# Uno_v1_0.net
KiCad netlist of a schematic drawn in EAGLE
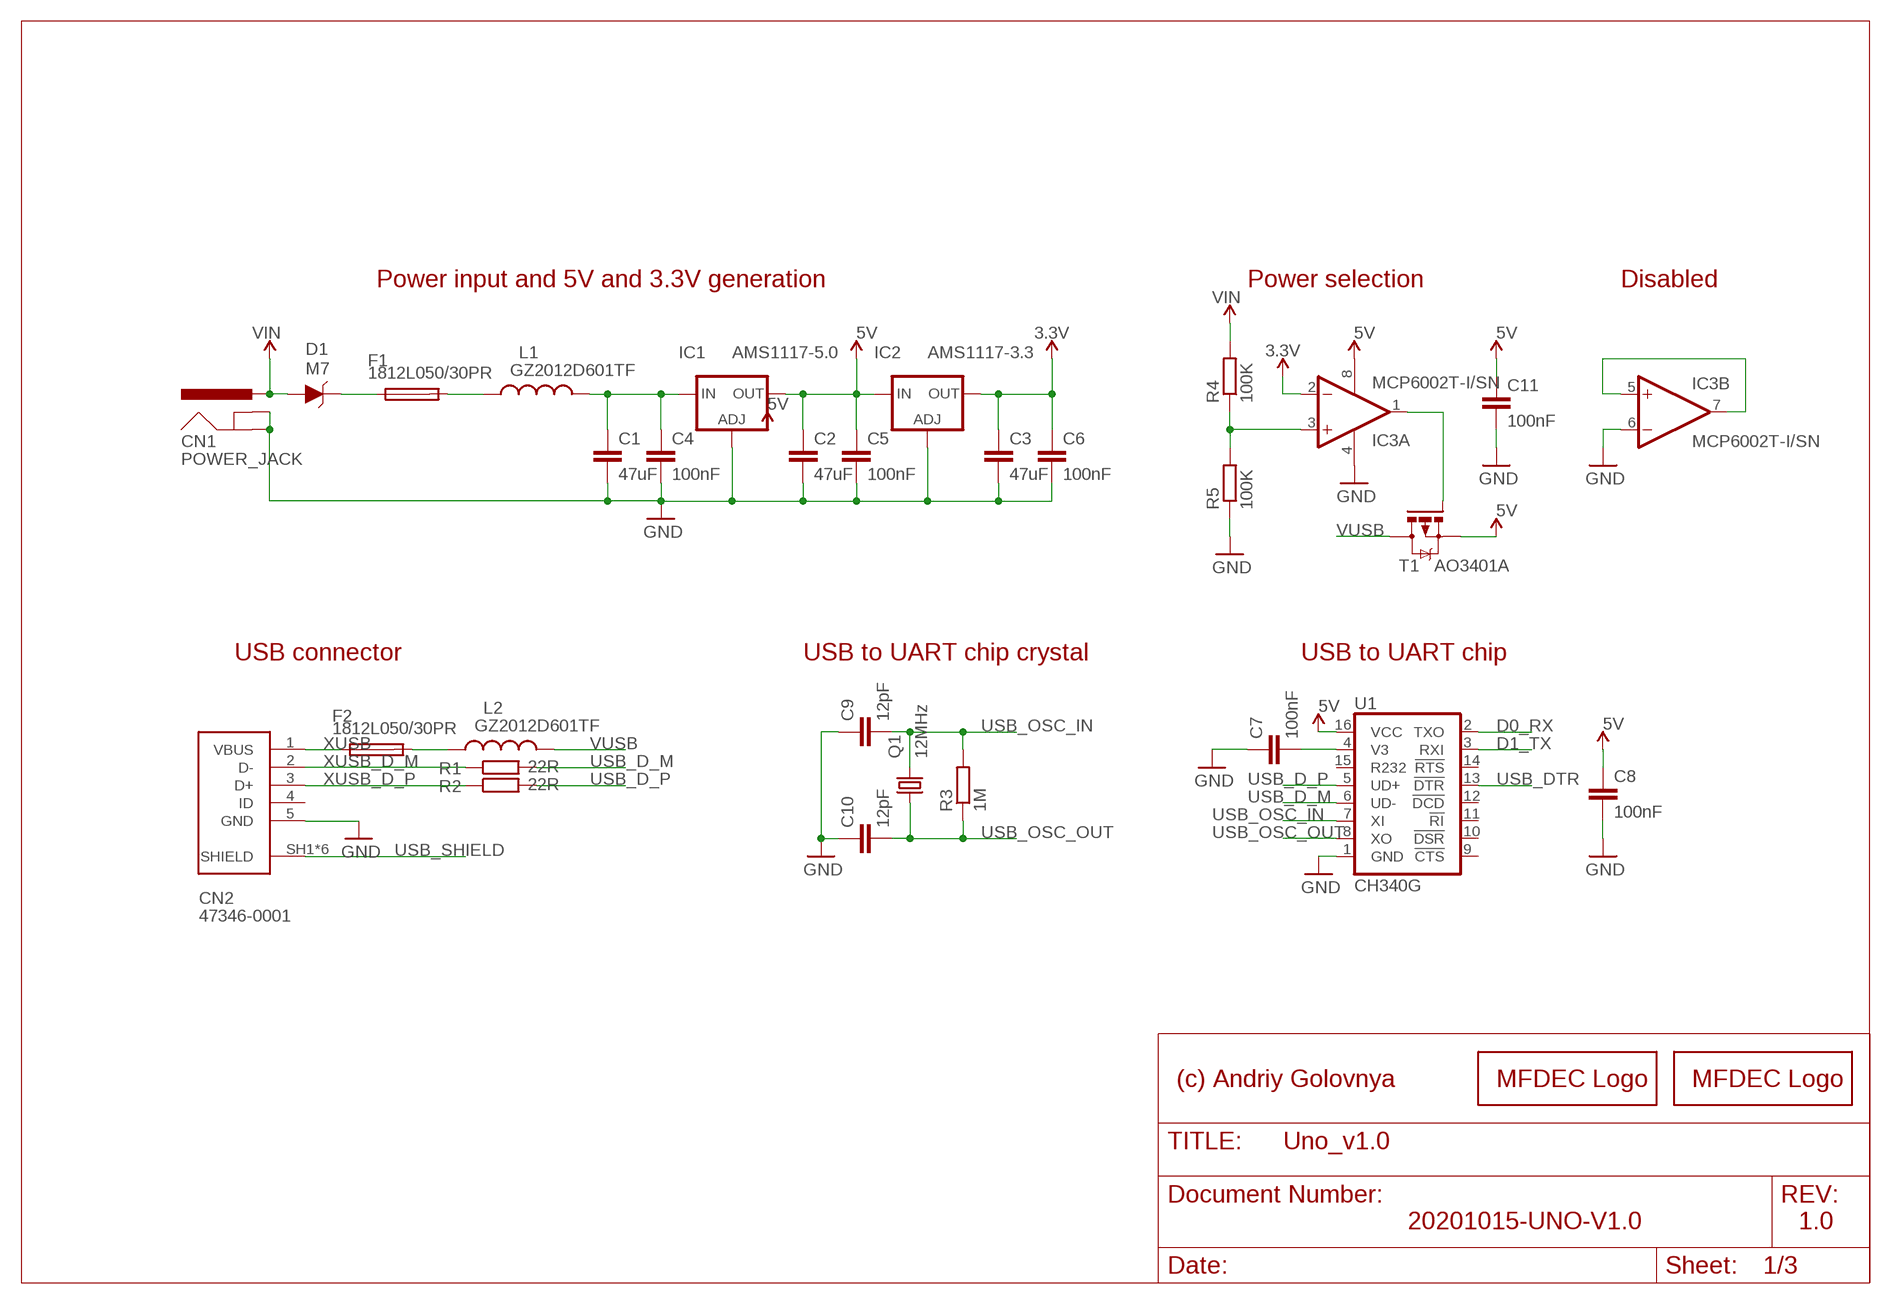
[diagram p0: schematic, sheet 1]
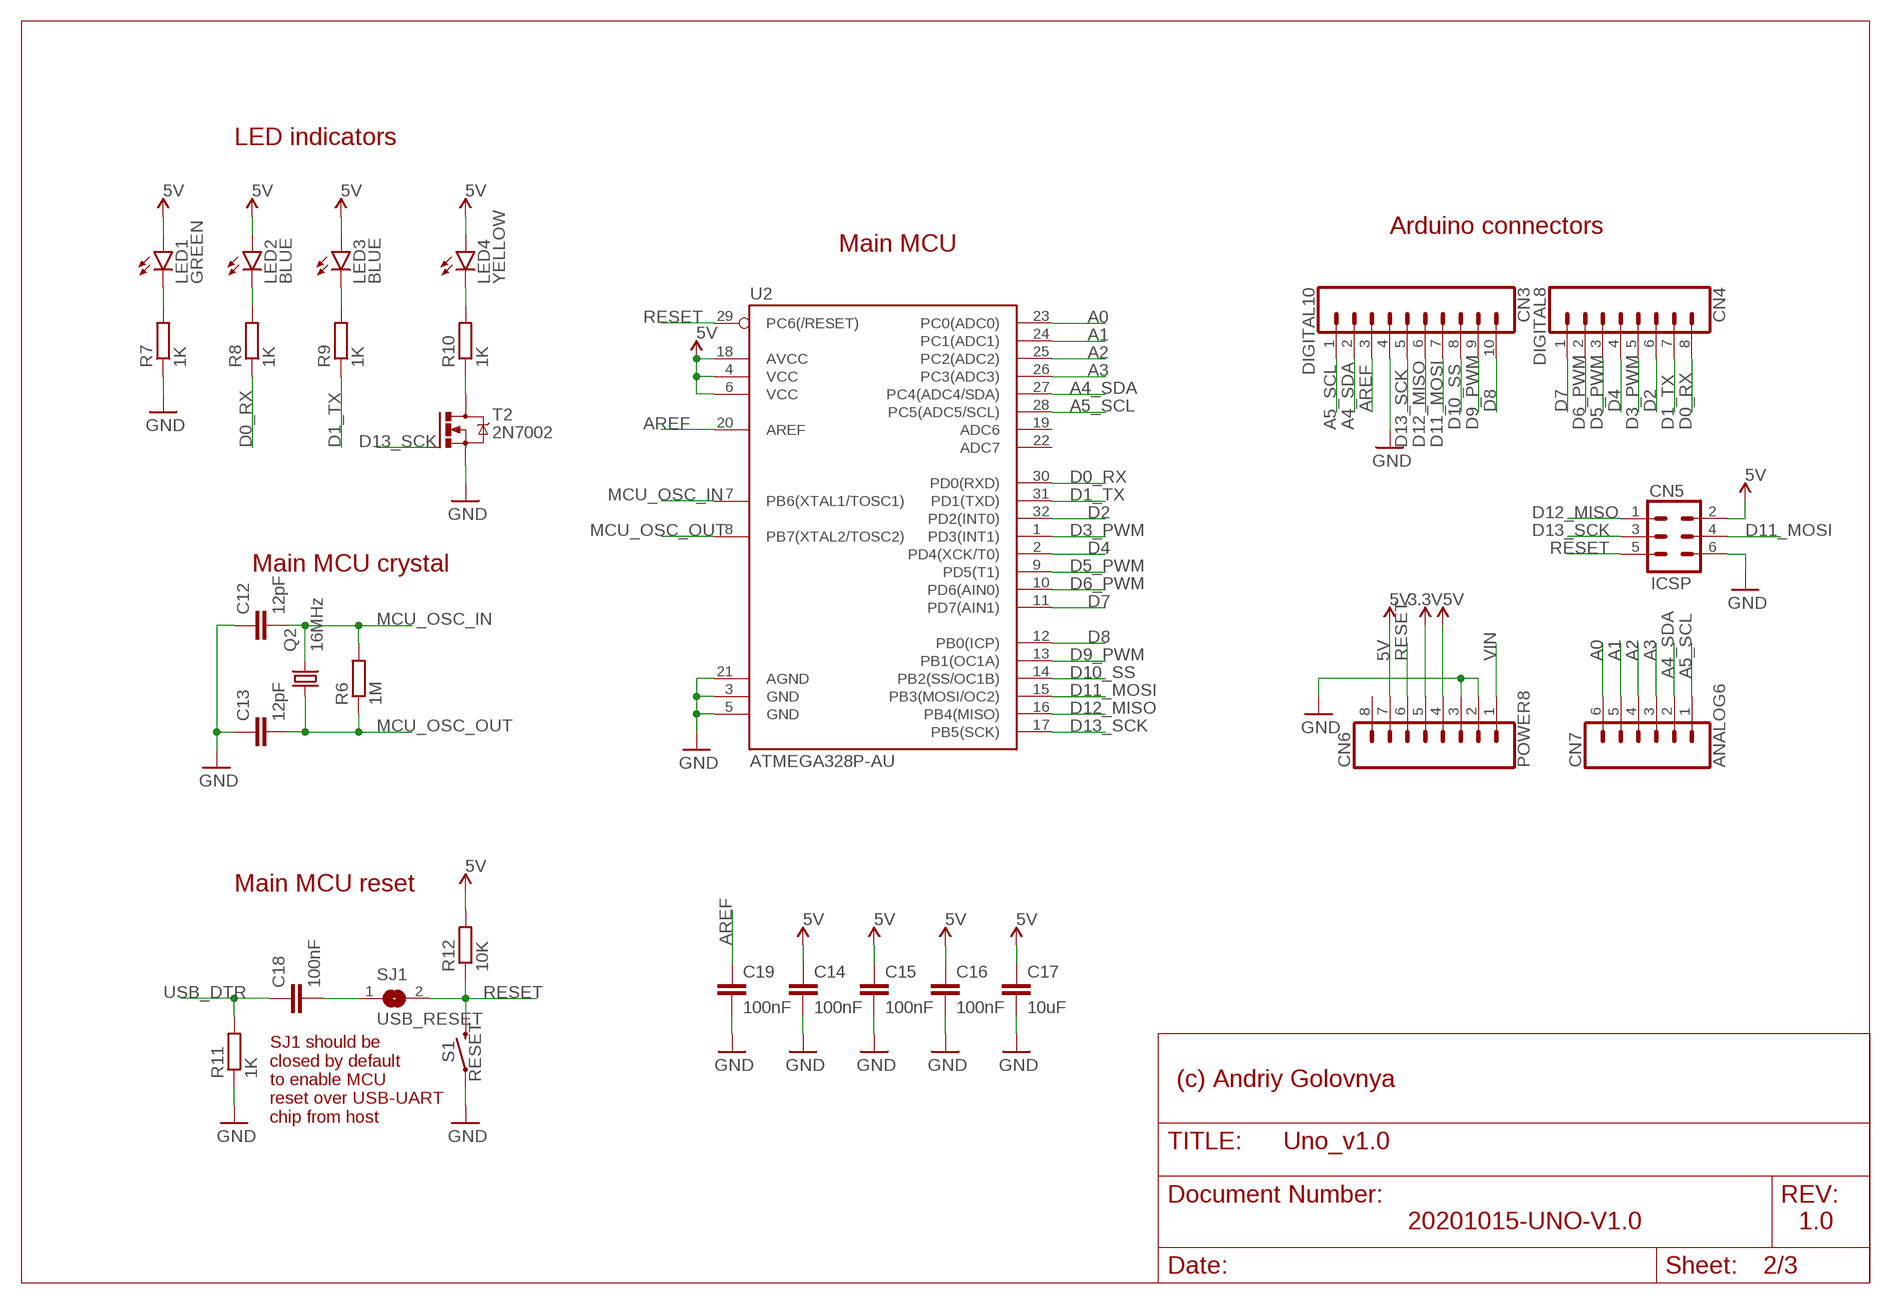
[diagram p1: schematic, sheet 2]
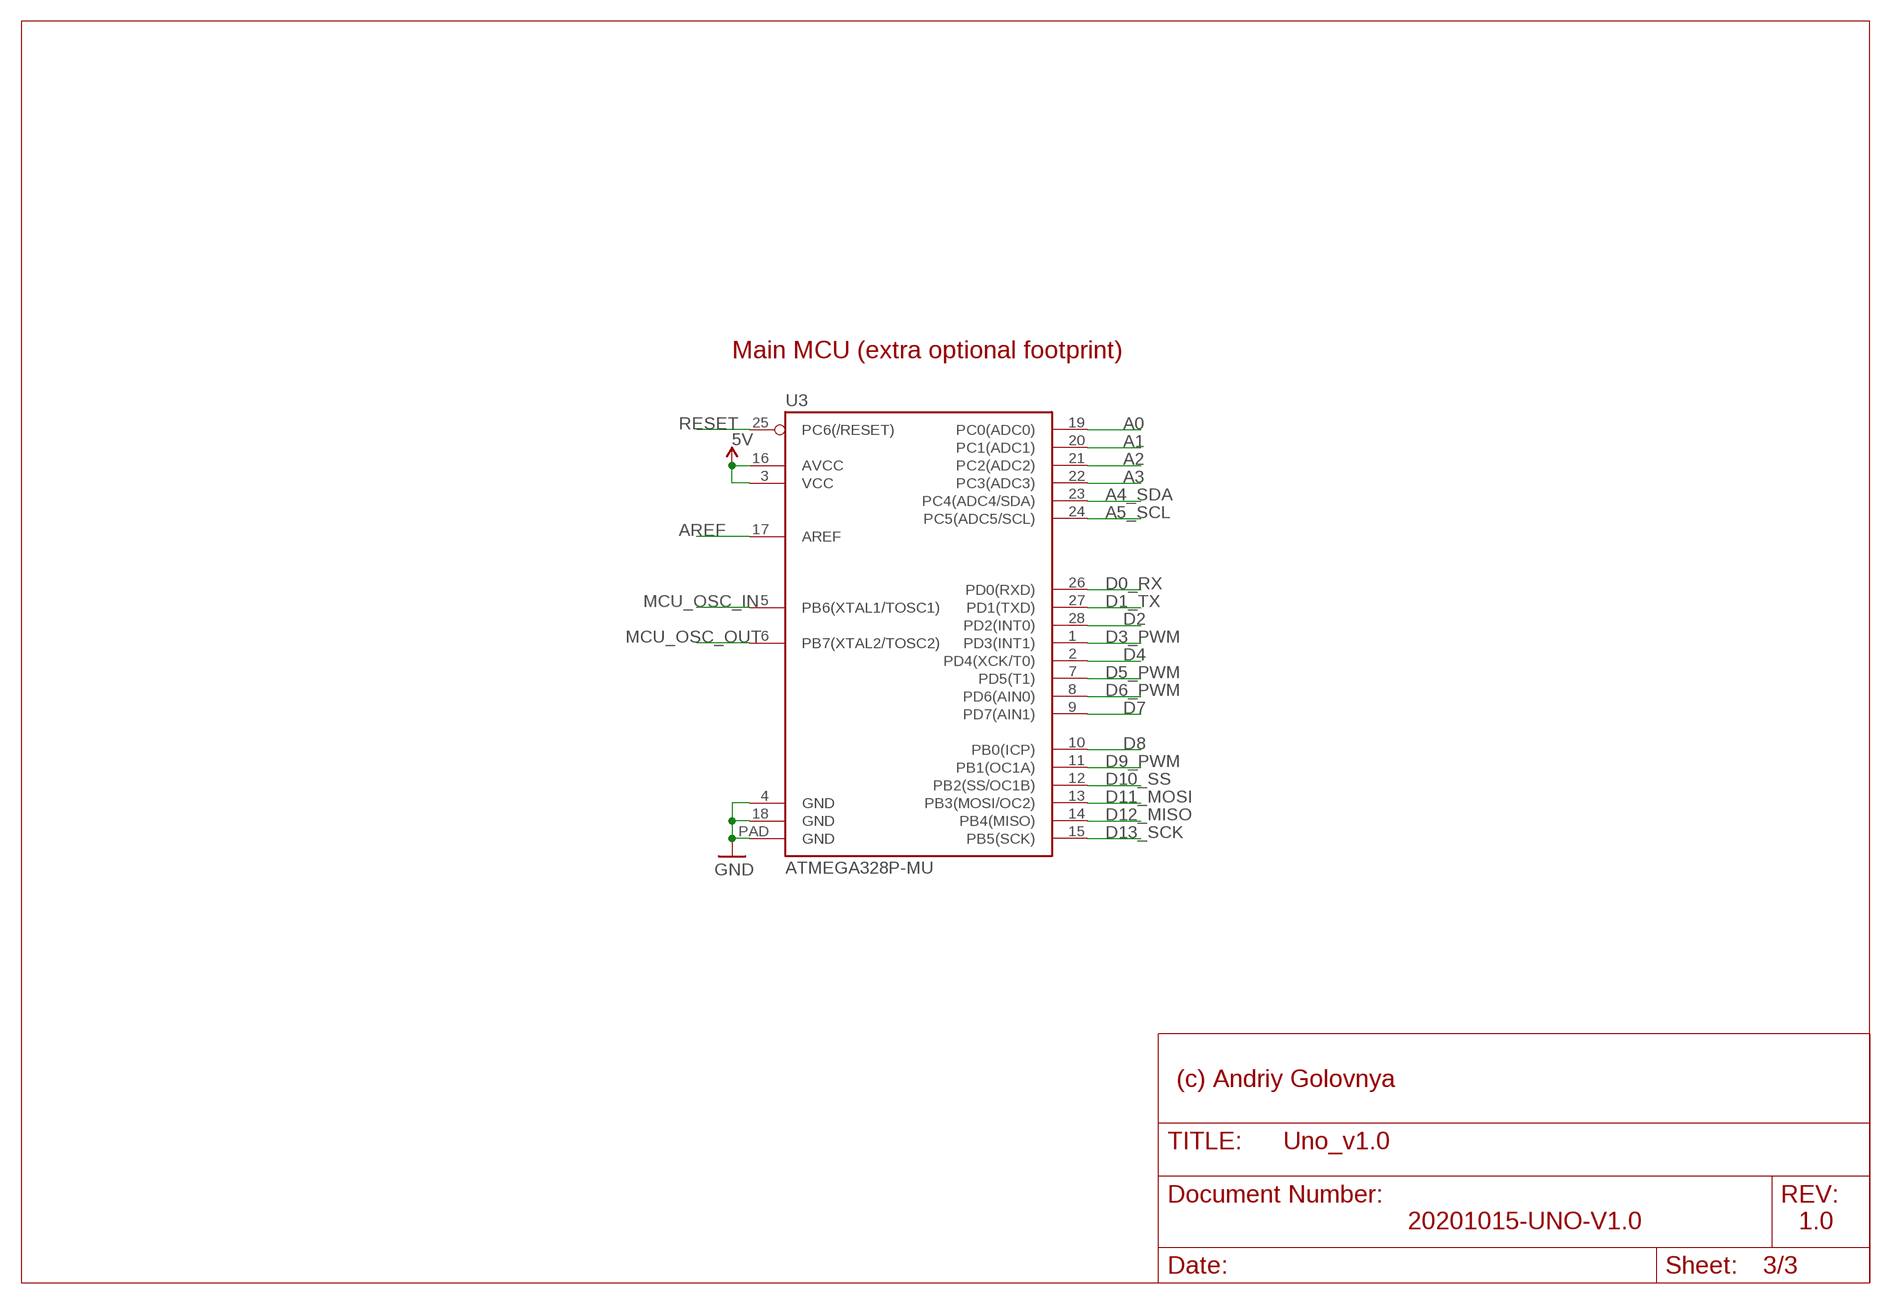
[diagram p2: schematic, sheet 3]

(export (version "E")
  (design (tool "Eeschema 10.0.6"))
  (components
    (comp (ref "U3")
      (value "ATMEGA328P-MU")
      (footprint "eagle-import:VQFN-28")
      (libsource (lib "eagle-import") (part "ATMEGA328P_VQFNVQFN"))
    )
    (comp (ref "C1")
      (value "47uF")
      (footprint "eagle-import:C1206")
      (libsource (lib "eagle-import") (part "C-EUC1206"))
    )
    (comp (ref "C2")
      (value "47uF")
      (footprint "eagle-import:C1206")
      (libsource (lib "eagle-import") (part "C-EUC1206"))
    )
    (comp (ref "C3")
      (value "47uF")
      (footprint "eagle-import:C1206")
      (libsource (lib "eagle-import") (part "C-EUC1206"))
    )
    (comp (ref "C4")
      (value "100nF")
      (footprint "eagle-import:C0402")
      (libsource (lib "eagle-import") (part "C-EUC0402"))
    )
    (comp (ref "C5")
      (value "100nF")
      (footprint "eagle-import:C0402")
      (libsource (lib "eagle-import") (part "C-EUC0402"))
    )
    (comp (ref "C6")
      (value "100nF")
      (footprint "eagle-import:C0402")
      (libsource (lib "eagle-import") (part "C-EUC0402"))
    )
    (comp (ref "C7")
      (value "100nF")
      (footprint "eagle-import:C0402")
      (libsource (lib "eagle-import") (part "C-EUC0402"))
    )
    (comp (ref "C8")
      (value "100nF")
      (footprint "eagle-import:C0402")
      (libsource (lib "eagle-import") (part "C-EUC0402"))
    )
    (comp (ref "C9")
      (value "12pF")
      (footprint "eagle-import:C0402")
      (libsource (lib "eagle-import") (part "C-EUC0402"))
    )
    (comp (ref "C10")
      (value "12pF")
      (footprint "eagle-import:C0402")
      (libsource (lib "eagle-import") (part "C-EUC0402"))
    )
    (comp (ref "C11")
      (value "100nF")
      (footprint "eagle-import:C0402")
      (libsource (lib "eagle-import") (part "C-EUC0402"))
    )
    (comp (ref "CN1")
      (value "POWER_JACK")
      (footprint "eagle-import:POWER_JACK_PTH")
      (libsource (lib "eagle-import") (part "POWER_JACK"))
    )
    (comp (ref "CN2")
      (value "47346-0001")
      (footprint "eagle-import:MOLEX_47346-0001")
      (fields (field (name "MANUFACTURER") "Molex"))
      (libsource (lib "eagle-import") (part "47346-0001"))
    )
    (comp (ref "D1")
      (value "M7")
      (footprint "eagle-import:WE-TVSP_DO-214AC_UNIDIRECTIONAL")
      (libsource (lib "eagle-import") (part "WE-TVSP_DO-214AC_400W_UNI_824500252"))
    )
    (comp (ref "F1")
      (value "1812L050/30PR")
      (footprint "eagle-import:MF-SMDF050")
      (libsource (lib "eagle-import") (part "MF-SMDF050"))
    )
    (comp (ref "F2")
      (value "1812L050/30PR")
      (footprint "eagle-import:MF-SMDF050")
      (libsource (lib "eagle-import") (part "MF-SMDF050"))
    )
    (comp (ref "IC1")
      (value "AMS1117-5.0")
      (footprint "eagle-import:SOT223")
      (libsource (lib "eagle-import") (part "LD117A?S50TR"))
    )
    (comp (ref "IC2")
      (value "AMS1117-3.3")
      (footprint "eagle-import:SOT223")
      (libsource (lib "eagle-import") (part "LD117A?S33TR"))
    )
    (comp (ref "IC3")
      (value "MCP6002T-I/SN")
      (footprint "eagle-import:SO08")
      (libsource (lib "eagle-import") (part "LMV358?MX"))
    )
    (comp (ref "L1")
      (value "GZ2012D601TF")
      (footprint "eagle-import:WE-CBA_0805(W=4)")
      (libsource (lib "eagle-import") (part "WE-CBA_0805_HC_782853102"))
    )
    (comp (ref "L2")
      (value "GZ2012D601TF")
      (footprint "eagle-import:WE-CBA_0805(W=4)")
      (libsource (lib "eagle-import") (part "WE-CBA_0805_HC_782853102"))
    )
    (comp (ref "LOGO1")
      (value "MFDECLOGO_SQ_10MM")
      (footprint "eagle-import:MFDEC_SQ_10MM")
      (libsource (lib "eagle-import") (part "MFDECLOGO_SQ_10MM"))
    )
    (comp (ref "LOGO2")
      (value "MFDECLOGO_L_40MM")
      (footprint "eagle-import:MFDEC_L_40MM")
      (libsource (lib "eagle-import") (part "MFDECLOGO_L_40MM"))
    )
    (comp (ref "Q1")
      (value "12MHz")
      (footprint "eagle-import:3.2X2.5_KX-7")
      (libsource (lib "eagle-import") (part "KX-7"))
    )
    (comp (ref "R1")
      (value "22R")
      (footprint "eagle-import:R0402")
      (libsource (lib "eagle-import") (part "R-EU_R0402"))
    )
    (comp (ref "R2")
      (value "22R")
      (footprint "eagle-import:R0402")
      (libsource (lib "eagle-import") (part "R-EU_R0402"))
    )
    (comp (ref "R3")
      (value "1M")
      (footprint "eagle-import:R0402")
      (libsource (lib "eagle-import") (part "R-EU_R0402"))
    )
    (comp (ref "R4")
      (value "100K")
      (footprint "eagle-import:R0402")
      (libsource (lib "eagle-import") (part "R-EU_R0402"))
    )
    (comp (ref "R5")
      (value "100K")
      (footprint "eagle-import:R0402")
      (libsource (lib "eagle-import") (part "R-EU_R0402"))
    )
    (comp (ref "T1")
      (value "AO3401A")
      (footprint "eagle-import:SOT23")
      (libsource (lib "eagle-import") (part "PMOSFETSOT23_"))
    )
    (comp (ref "U1")
      (value "CH340G")
      (footprint "eagle-import:SO016")
      (libsource (lib "eagle-import") (part "CH340GSMD"))
    )
    (comp (ref "C12")
      (value "12pF")
      (footprint "eagle-import:C0402")
      (libsource (lib "eagle-import") (part "C-EUC0402"))
    )
    (comp (ref "C13")
      (value "12pF")
      (footprint "eagle-import:C0402")
      (libsource (lib "eagle-import") (part "C-EUC0402"))
    )
    (comp (ref "C14")
      (value "100nF")
      (footprint "eagle-import:C0402")
      (libsource (lib "eagle-import") (part "C-EUC0402"))
    )
    (comp (ref "C15")
      (value "100nF")
      (footprint "eagle-import:C0402")
      (libsource (lib "eagle-import") (part "C-EUC0402"))
    )
    (comp (ref "C16")
      (value "100nF")
      (footprint "eagle-import:C0402")
      (libsource (lib "eagle-import") (part "C-EUC0402"))
    )
    (comp (ref "C17")
      (value "10uF")
      (footprint "eagle-import:C0805")
      (libsource (lib "eagle-import") (part "C-EUC0805"))
    )
    (comp (ref "C18")
      (value "100nF")
      (footprint "eagle-import:C0402")
      (libsource (lib "eagle-import") (part "C-EUC0402"))
    )
    (comp (ref "C19")
      (value "100nF")
      (footprint "eagle-import:C0402")
      (libsource (lib "eagle-import") (part "C-EUC0402"))
    )
    (comp (ref "CN3")
      (value "DIGITAL10")
      (footprint "eagle-import:1X10_NO_SILK")
      (libsource (lib "eagle-import") (part "CONN_10NO_SILK_PTH_FEMALE"))
    )
    (comp (ref "CN4")
      (value "DIGITAL8")
      (footprint "eagle-import:1X08_NO_SILK")
      (libsource (lib "eagle-import") (part "CONN_08NO_SILK_FEMALE_PTH"))
    )
    (comp (ref "CN5")
      (value "ICSP")
      (footprint "eagle-import:2X3-NS")
      (libsource (lib "eagle-import") (part "CONN_03X2NO_SILK"))
    )
    (comp (ref "CN6")
      (value "POWER8")
      (footprint "eagle-import:1X08_NO_SILK")
      (libsource (lib "eagle-import") (part "CONN_08NO_SILK_FEMALE_PTH"))
    )
    (comp (ref "CN7")
      (value "ANALOG6")
      (footprint "eagle-import:1X06_NO_SILK")
      (libsource (lib "eagle-import") (part "CONN_06NO_SILK_FEMALE_PTH"))
    )
    (comp (ref "LED1")
      (value "GREEN")
      (footprint "eagle-import:SML0603")
      (libsource (lib "eagle-import") (part "LEDSML0603"))
    )
    (comp (ref "LED2")
      (value "BLUE")
      (footprint "eagle-import:SML0603")
      (libsource (lib "eagle-import") (part "LEDSML0603"))
    )
    (comp (ref "LED3")
      (value "BLUE")
      (footprint "eagle-import:SML0603")
      (libsource (lib "eagle-import") (part "LEDSML0603"))
    )
    (comp (ref "LED4")
      (value "YELLOW")
      (footprint "eagle-import:SML0603")
      (libsource (lib "eagle-import") (part "LEDSML0603"))
    )
    (comp (ref "Q2")
      (value "16MHz")
      (footprint "eagle-import:3.2X2.5_KX-7")
      (libsource (lib "eagle-import") (part "KX-7"))
    )
    (comp (ref "R6")
      (value "1M")
      (footprint "eagle-import:R0402")
      (libsource (lib "eagle-import") (part "R-EU_R0402"))
    )
    (comp (ref "R7")
      (value "1K")
      (footprint "eagle-import:R0402")
      (libsource (lib "eagle-import") (part "R-EU_R0402"))
    )
    (comp (ref "R8")
      (value "1K")
      (footprint "eagle-import:R0402")
      (libsource (lib "eagle-import") (part "R-EU_R0402"))
    )
    (comp (ref "R9")
      (value "1K")
      (footprint "eagle-import:R0402")
      (libsource (lib "eagle-import") (part "R-EU_R0402"))
    )
    (comp (ref "R10")
      (value "1K")
      (footprint "eagle-import:R0402")
      (libsource (lib "eagle-import") (part "R-EU_R0402"))
    )
    (comp (ref "R11")
      (value "1K")
      (footprint "eagle-import:R0402")
      (libsource (lib "eagle-import") (part "R-EU_R0402"))
    )
    (comp (ref "R12")
      (value "10K")
      (footprint "eagle-import:R0402")
      (libsource (lib "eagle-import") (part "R-EU_R0402"))
    )
    (comp (ref "S1")
      (value "RESET")
      (footprint "eagle-import:TACTILE_SWITCH_SMD_5.2MM")
      (libsource (lib "eagle-import") (part "MOMENTARY-SWITCH-SPST-SMD-5.2MM"))
    )
    (comp (ref "SJ1")
      (value "USB_RESET")
      (footprint "eagle-import:SJ")
      (libsource (lib "eagle-import") (part "SJ"))
    )
    (comp (ref "T2")
      (value "2N7002")
      (footprint "eagle-import:SOT23")
      (libsource (lib "eagle-import") (part "NMOSFETSOT23_"))
    )
    (comp (ref "U2")
      (value "ATMEGA328P-AU")
      (footprint "eagle-import:TQFP32-08")
      (libsource (lib "eagle-import") (part "ATMEGA328P_TQFP"))
    )
  )
  (nets
    (net (code "1") (name "3.3V") (class "Default")
      (node (ref "C3") (pin "1") (pinfunction "1_1") (pintype "passive"))
      (node (ref "C6") (pin "1") (pinfunction "1_1") (pintype "passive"))
      (node (ref "CN6") (pin "5") (pinfunction "5_5") (pintype "passive"))
      (node (ref "IC2") (pin "4") (pinfunction "OUT_4") (pintype "passive"))
      (node (ref "IC3") (pin "2") (pinfunction "-IN_2") (pintype "input"))
    )
    (net (code "2") (name "5V") (class "Default")
      (node (ref "C11") (pin "1") (pinfunction "1_1") (pintype "passive"))
      (node (ref "C14") (pin "1") (pinfunction "1_1") (pintype "passive"))
      (node (ref "C15") (pin "1") (pinfunction "1_1") (pintype "passive"))
      (node (ref "C16") (pin "1") (pinfunction "1_1") (pintype "passive"))
      (node (ref "C17") (pin "1") (pinfunction "1_1") (pintype "passive"))
      (node (ref "C2") (pin "1") (pinfunction "1_1") (pintype "passive"))
      (node (ref "C5") (pin "1") (pinfunction "1_1") (pintype "passive"))
      (node (ref "C8") (pin "1") (pinfunction "1_1") (pintype "passive"))
      (node (ref "CN5") (pin "2") (pinfunction "2_2") (pintype "bidirectional"))
      (node (ref "CN6") (pin "4") (pinfunction "4_4") (pintype "passive"))
      (node (ref "CN6") (pin "7") (pinfunction "7_7") (pintype "passive"))
      (node (ref "IC1") (pin "4") (pinfunction "OUT_4") (pintype "passive"))
      (node (ref "IC2") (pin "3") (pinfunction "IN_3") (pintype "input"))
      (node (ref "IC3") (pin "8") (pinfunction "V+_8") (pintype "power_in"))
      (node (ref "LED1") (pin "A") (pinfunction "A_A") (pintype "passive"))
      (node (ref "LED2") (pin "A") (pinfunction "A_A") (pintype "passive"))
      (node (ref "LED3") (pin "A") (pinfunction "A_A") (pintype "passive"))
      (node (ref "LED4") (pin "A") (pinfunction "A_A") (pintype "passive"))
      (node (ref "R12") (pin "2") (pinfunction "2_2") (pintype "passive"))
      (node (ref "T1") (pin "2") (pinfunction "S_2") (pintype "passive"))
      (node (ref "U1") (pin "16") (pinfunction "VCC_16") (pintype "bidirectional"))
      (node (ref "U2") (pin "18") (pinfunction "AVCC_18") (pintype "bidirectional"))
      (node (ref "U2") (pin "4") (pinfunction "VCC_4") (pintype "bidirectional"))
      (node (ref "U2") (pin "6") (pinfunction "VCC_6") (pintype "bidirectional"))
      (node (ref "U3") (pin "16") (pinfunction "AVCC_16") (pintype "bidirectional"))
      (node (ref "U3") (pin "3") (pinfunction "VCC_3") (pintype "bidirectional"))
    )
    (net (code "3") (name "A0") (class "Default")
      (node (ref "CN7") (pin "6") (pinfunction "6_6") (pintype "passive"))
      (node (ref "U2") (pin "23") (pinfunction "PC0(ADC0)_23") (pintype "bidirectional"))
      (node (ref "U3") (pin "19") (pinfunction "PC0(ADC0)_19") (pintype "bidirectional"))
    )
    (net (code "4") (name "A1") (class "Default")
      (node (ref "CN7") (pin "5") (pinfunction "5_5") (pintype "passive"))
      (node (ref "U2") (pin "24") (pinfunction "PC1(ADC1)_24") (pintype "bidirectional"))
      (node (ref "U3") (pin "20") (pinfunction "PC1(ADC1)_20") (pintype "bidirectional"))
    )
    (net (code "5") (name "A2") (class "Default")
      (node (ref "CN7") (pin "4") (pinfunction "4_4") (pintype "passive"))
      (node (ref "U2") (pin "25") (pinfunction "PC2(ADC2)_25") (pintype "bidirectional"))
      (node (ref "U3") (pin "21") (pinfunction "PC2(ADC2)_21") (pintype "bidirectional"))
    )
    (net (code "6") (name "A3") (class "Default")
      (node (ref "CN7") (pin "3") (pinfunction "3_3") (pintype "passive"))
      (node (ref "U2") (pin "26") (pinfunction "PC3(ADC3)_26") (pintype "bidirectional"))
      (node (ref "U3") (pin "22") (pinfunction "PC3(ADC3)_22") (pintype "bidirectional"))
    )
    (net (code "7") (name "A4_SDA") (class "Default")
      (node (ref "CN3") (pin "2") (pinfunction "2_2") (pintype "passive"))
      (node (ref "CN7") (pin "2") (pinfunction "2_2") (pintype "passive"))
      (node (ref "U2") (pin "27") (pinfunction "PC4(ADC4/SDA)_27") (pintype "bidirectional"))
      (node (ref "U3") (pin "23") (pinfunction "PC4(ADC4/SDA)_23") (pintype "bidirectional"))
    )
    (net (code "8") (name "A5_SCL") (class "Default")
      (node (ref "CN3") (pin "1") (pinfunction "1_1") (pintype "passive"))
      (node (ref "CN7") (pin "1") (pinfunction "1_1") (pintype "passive"))
      (node (ref "U2") (pin "28") (pinfunction "PC5(ADC5/SCL)_28") (pintype "bidirectional"))
      (node (ref "U3") (pin "24") (pinfunction "PC5(ADC5/SCL)_24") (pintype "bidirectional"))
    )
    (net (code "9") (name "AREF") (class "Default")
      (node (ref "C19") (pin "1") (pinfunction "1_1") (pintype "passive"))
      (node (ref "CN3") (pin "3") (pinfunction "3_3") (pintype "passive"))
      (node (ref "U2") (pin "20") (pinfunction "AREF_20") (pintype "bidirectional"))
      (node (ref "U3") (pin "17") (pinfunction "AREF_17") (pintype "bidirectional"))
    )
    (net (code "10") (name "D0_RX") (class "Default")
      (node (ref "CN4") (pin "8") (pinfunction "8_8") (pintype "passive"))
      (node (ref "R8") (pin "1") (pinfunction "1_1") (pintype "passive"))
      (node (ref "U1") (pin "2") (pinfunction "TXO_2") (pintype "bidirectional"))
      (node (ref "U2") (pin "30") (pinfunction "PD0(RXD)_30") (pintype "bidirectional"))
      (node (ref "U3") (pin "26") (pinfunction "PD0(RXD)_26") (pintype "bidirectional"))
    )
    (net (code "11") (name "D1_TX") (class "Default")
      (node (ref "CN4") (pin "7") (pinfunction "7_7") (pintype "passive"))
      (node (ref "R9") (pin "1") (pinfunction "1_1") (pintype "passive"))
      (node (ref "U1") (pin "3") (pinfunction "RXI_3") (pintype "bidirectional"))
      (node (ref "U2") (pin "31") (pinfunction "PD1(TXD)_31") (pintype "bidirectional"))
      (node (ref "U3") (pin "27") (pinfunction "PD1(TXD)_27") (pintype "bidirectional"))
    )
    (net (code "12") (name "D2") (class "Default")
      (node (ref "CN4") (pin "6") (pinfunction "6_6") (pintype "passive"))
      (node (ref "U2") (pin "32") (pinfunction "PD2(INT0)_32") (pintype "bidirectional"))
      (node (ref "U3") (pin "28") (pinfunction "PD2(INT0)_28") (pintype "bidirectional"))
    )
    (net (code "13") (name "D3_PWM") (class "Default")
      (node (ref "CN4") (pin "5") (pinfunction "5_5") (pintype "passive"))
      (node (ref "U2") (pin "1") (pinfunction "PD3(INT1)_1") (pintype "bidirectional"))
      (node (ref "U3") (pin "1") (pinfunction "PD3(INT1)_1") (pintype "bidirectional"))
    )
    (net (code "14") (name "D4") (class "Default")
      (node (ref "CN4") (pin "4") (pinfunction "4_4") (pintype "passive"))
      (node (ref "U2") (pin "2") (pinfunction "PD4(XCK/T0)_2") (pintype "bidirectional"))
      (node (ref "U3") (pin "2") (pinfunction "PD4(XCK/T0)_2") (pintype "bidirectional"))
    )
    (net (code "15") (name "D5_PWM") (class "Default")
      (node (ref "CN4") (pin "3") (pinfunction "3_3") (pintype "passive"))
      (node (ref "U2") (pin "9") (pinfunction "PD5(T1)_9") (pintype "bidirectional"))
      (node (ref "U3") (pin "7") (pinfunction "PD5(T1)_7") (pintype "bidirectional"))
    )
    (net (code "16") (name "D6_PWM") (class "Default")
      (node (ref "CN4") (pin "2") (pinfunction "2_2") (pintype "passive"))
      (node (ref "U2") (pin "10") (pinfunction "PD6(AIN0)_10") (pintype "bidirectional"))
      (node (ref "U3") (pin "8") (pinfunction "PD6(AIN0)_8") (pintype "bidirectional"))
    )
    (net (code "17") (name "D7") (class "Default")
      (node (ref "CN4") (pin "1") (pinfunction "1_1") (pintype "passive"))
      (node (ref "U2") (pin "11") (pinfunction "PD7(AIN1)_11") (pintype "bidirectional"))
      (node (ref "U3") (pin "9") (pinfunction "PD7(AIN1)_9") (pintype "bidirectional"))
    )
    (net (code "18") (name "D8") (class "Default")
      (node (ref "CN3") (pin "10") (pinfunction "10_10") (pintype "passive"))
      (node (ref "U2") (pin "12") (pinfunction "PB0(ICP)_12") (pintype "bidirectional"))
      (node (ref "U3") (pin "10") (pinfunction "PB0(ICP)_10") (pintype "bidirectional"))
    )
    (net (code "19") (name "D9_PWM") (class "Default")
      (node (ref "CN3") (pin "9") (pinfunction "9_9") (pintype "passive"))
      (node (ref "U2") (pin "13") (pinfunction "PB1(OC1A)_13") (pintype "bidirectional"))
      (node (ref "U3") (pin "11") (pinfunction "PB1(OC1A)_11") (pintype "bidirectional"))
    )
    (net (code "20") (name "D10_SS") (class "Default")
      (node (ref "CN3") (pin "8") (pinfunction "8_8") (pintype "passive"))
      (node (ref "U2") (pin "14") (pinfunction "PB2(SS/OC1B)_14") (pintype "bidirectional"))
      (node (ref "U3") (pin "12") (pinfunction "PB2(SS/OC1B)_12") (pintype "bidirectional"))
    )
    (net (code "21") (name "D11_MOSI") (class "Default")
      (node (ref "CN3") (pin "7") (pinfunction "7_7") (pintype "passive"))
      (node (ref "CN5") (pin "4") (pinfunction "4_4") (pintype "bidirectional"))
      (node (ref "U2") (pin "15") (pinfunction "PB3(MOSI/OC2)_15") (pintype "bidirectional"))
      (node (ref "U3") (pin "13") (pinfunction "PB3(MOSI/OC2)_13") (pintype "bidirectional"))
    )
    (net (code "22") (name "D12_MISO") (class "Default")
      (node (ref "CN3") (pin "6") (pinfunction "6_6") (pintype "passive"))
      (node (ref "CN5") (pin "1") (pinfunction "1_1") (pintype "bidirectional"))
      (node (ref "U2") (pin "16") (pinfunction "PB4(MISO)_16") (pintype "bidirectional"))
      (node (ref "U3") (pin "14") (pinfunction "PB4(MISO)_14") (pintype "bidirectional"))
    )
    (net (code "23") (name "D13_SCK") (class "Default")
      (node (ref "CN3") (pin "5") (pinfunction "5_5") (pintype "passive"))
      (node (ref "CN5") (pin "3") (pinfunction "3_3") (pintype "bidirectional"))
      (node (ref "T2") (pin "1") (pinfunction "G_1") (pintype "passive"))
      (node (ref "U2") (pin "17") (pinfunction "PB5(SCK)_17") (pintype "bidirectional"))
      (node (ref "U3") (pin "15") (pinfunction "PB5(SCK)_15") (pintype "bidirectional"))
    )
    (net (code "24") (name "GND") (class "Default")
      (node (ref "C1") (pin "2") (pinfunction "2_2") (pintype "passive"))
      (node (ref "C10") (pin "1") (pinfunction "1_1") (pintype "passive"))
      (node (ref "C11") (pin "2") (pinfunction "2_2") (pintype "passive"))
      (node (ref "C12") (pin "1") (pinfunction "1_1") (pintype "passive"))
      (node (ref "C13") (pin "1") (pinfunction "1_1") (pintype "passive"))
      (node (ref "C14") (pin "2") (pinfunction "2_2") (pintype "passive"))
      (node (ref "C15") (pin "2") (pinfunction "2_2") (pintype "passive"))
      (node (ref "C16") (pin "2") (pinfunction "2_2") (pintype "passive"))
      (node (ref "C17") (pin "2") (pinfunction "2_2") (pintype "passive"))
      (node (ref "C19") (pin "2") (pinfunction "2_2") (pintype "passive"))
      (node (ref "C2") (pin "2") (pinfunction "2_2") (pintype "passive"))
      (node (ref "C3") (pin "2") (pinfunction "2_2") (pintype "passive"))
      (node (ref "C4") (pin "2") (pinfunction "2_2") (pintype "passive"))
      (node (ref "C5") (pin "2") (pinfunction "2_2") (pintype "passive"))
      (node (ref "C6") (pin "2") (pinfunction "2_2") (pintype "passive"))
      (node (ref "C7") (pin "1") (pinfunction "1_1") (pintype "passive"))
      (node (ref "C8") (pin "2") (pinfunction "2_2") (pintype "passive"))
      (node (ref "C9") (pin "1") (pinfunction "1_1") (pintype "passive"))
      (node (ref "CN1") (pin "GND") (pinfunction "GND_GND") (pintype "bidirectional"))
      (node (ref "CN1") (pin "GNDBREAK") (pinfunction "GNDBREAK_GNDBREAK") (pintype "bidirectional"))
      (node (ref "CN2") (pin "5") (pinfunction "GND_5") (pintype "power_in"))
      (node (ref "CN3") (pin "4") (pinfunction "4_4") (pintype "passive"))
      (node (ref "CN5") (pin "6") (pinfunction "6_6") (pintype "bidirectional"))
      (node (ref "CN6") (pin "2") (pinfunction "2_2") (pintype "passive"))
      (node (ref "CN6") (pin "3") (pinfunction "3_3") (pintype "passive"))
      (node (ref "IC1") (pin "1") (pinfunction "ADJ_1") (pintype "input"))
      (node (ref "IC2") (pin "1") (pinfunction "ADJ_1") (pintype "input"))
      (node (ref "IC3") (pin "4") (pinfunction "V-_4") (pintype "power_in"))
      (node (ref "IC3") (pin "6") (pinfunction "-IN_6") (pintype "input"))
      (node (ref "R11") (pin "1") (pinfunction "1_1") (pintype "passive"))
      (node (ref "R5") (pin "1") (pinfunction "1_1") (pintype "passive"))
      (node (ref "R7") (pin "1") (pinfunction "1_1") (pintype "passive"))
      (node (ref "S1") (pin "1") (pinfunction "1_1") (pintype "passive"))
      (node (ref "T2") (pin "2") (pinfunction "S_2") (pintype "passive"))
      (node (ref "U1") (pin "1") (pinfunction "GND_1") (pintype "bidirectional"))
      (node (ref "U2") (pin "21") (pinfunction "AGND_21") (pintype "bidirectional"))
      (node (ref "U2") (pin "3") (pinfunction "GND_3") (pintype "bidirectional"))
      (node (ref "U2") (pin "5") (pinfunction "GND_5") (pintype "bidirectional"))
      (node (ref "U3") (pin "18") (pinfunction "GND_18") (pintype "bidirectional"))
      (node (ref "U3") (pin "4") (pinfunction "GND_4") (pintype "bidirectional"))
      (node (ref "U3") (pin "PAD") (pinfunction "GND_PAD") (pintype "bidirectional"))
    )
    (net (code "25") (name "MCU_OSC_IN") (class "Default")
      (node (ref "C12") (pin "2") (pinfunction "2_2") (pintype "passive"))
      (node (ref "Q2") (pin "3") (pinfunction "2_3") (pintype "passive"))
      (node (ref "R6") (pin "2") (pinfunction "2_2") (pintype "passive"))
      (node (ref "U2") (pin "7") (pinfunction "PB6(XTAL1/TOSC1)_7") (pintype "bidirectional"))
      (node (ref "U3") (pin "5") (pinfunction "PB6(XTAL1/TOSC1)_5") (pintype "bidirectional"))
    )
    (net (code "26") (name "MCU_OSC_OUT") (class "Default")
      (node (ref "C13") (pin "2") (pinfunction "2_2") (pintype "passive"))
      (node (ref "Q2") (pin "1") (pinfunction "1_1") (pintype "passive"))
      (node (ref "R6") (pin "1") (pinfunction "1_1") (pintype "passive"))
      (node (ref "U2") (pin "8") (pinfunction "PB7(XTAL2/TOSC2)_8") (pintype "bidirectional"))
      (node (ref "U3") (pin "6") (pinfunction "PB7(XTAL2/TOSC2)_6") (pintype "bidirectional"))
    )
    (net (code "27") (name "Net-(C18-Pad2)") (class "Default")
      (node (ref "C18") (pin "2") (pinfunction "2_2") (pintype "passive"))
      (node (ref "SJ1") (pin "1") (pinfunction "1_1") (pintype "passive"))
    )
    (net (code "28") (name "Net-(D1-C)") (class "Default")
      (node (ref "D1") (pin "1") (pinfunction "C_1") (pintype "passive"))
      (node (ref "F1") (pin "1") (pinfunction "1_1") (pintype "passive"))
    )
    (net (code "29") (name "Net-(F1-Pad2)") (class "Default")
      (node (ref "F1") (pin "2") (pinfunction "2_2") (pintype "passive"))
      (node (ref "L1") (pin "1") (pinfunction "1_1") (pintype "passive"))
    )
    (net (code "30") (name "Net-(F2-Pad2)") (class "Default")
      (node (ref "F2") (pin "2") (pinfunction "2_2") (pintype "passive"))
      (node (ref "L2") (pin "1") (pinfunction "1_1") (pintype "passive"))
    )
    (net (code "31") (name "Net-(IC1-IN)") (class "Default")
      (node (ref "C1") (pin "1") (pinfunction "1_1") (pintype "passive"))
      (node (ref "C4") (pin "1") (pinfunction "1_1") (pintype "passive"))
      (node (ref "IC1") (pin "3") (pinfunction "IN_3") (pintype "input"))
      (node (ref "L1") (pin "2") (pinfunction "2_2") (pintype "passive"))
    )
    (net (code "32") (name "Net-(IC3A-+IN)") (class "Default")
      (node (ref "IC3") (pin "3") (pinfunction "+IN_3") (pintype "input"))
      (node (ref "R4") (pin "1") (pinfunction "1_1") (pintype "passive"))
      (node (ref "R5") (pin "2") (pinfunction "2_2") (pintype "passive"))
    )
    (net (code "33") (name "Net-(IC3A-OUT)") (class "Default")
      (node (ref "IC3") (pin "1") (pinfunction "OUT_1") (pintype "output"))
      (node (ref "T1") (pin "1") (pinfunction "G_1") (pintype "passive"))
    )
    (net (code "34") (name "Net-(IC3B-+IN)") (class "Default")
      (node (ref "IC3") (pin "5") (pinfunction "+IN_5") (pintype "input"))
      (node (ref "IC3") (pin "7") (pinfunction "OUT_7") (pintype "output"))
    )
    (net (code "35") (name "Net-(LED1-PadC)") (class "Default")
      (node (ref "LED1") (pin "C") (pinfunction "C_C") (pintype "passive"))
      (node (ref "R7") (pin "2") (pinfunction "2_2") (pintype "passive"))
    )
    (net (code "36") (name "Net-(LED2-PadC)") (class "Default")
      (node (ref "LED2") (pin "C") (pinfunction "C_C") (pintype "passive"))
      (node (ref "R8") (pin "2") (pinfunction "2_2") (pintype "passive"))
    )
    (net (code "37") (name "Net-(LED3-PadC)") (class "Default")
      (node (ref "LED3") (pin "C") (pinfunction "C_C") (pintype "passive"))
      (node (ref "R9") (pin "2") (pinfunction "2_2") (pintype "passive"))
    )
    (net (code "38") (name "Net-(LED4-PadC)") (class "Default")
      (node (ref "LED4") (pin "C") (pinfunction "C_C") (pintype "passive"))
      (node (ref "R10") (pin "2") (pinfunction "2_2") (pintype "passive"))
    )
    (net (code "39") (name "Net-(T2-D)") (class "Default")
      (node (ref "R10") (pin "1") (pinfunction "1_1") (pintype "passive"))
      (node (ref "T2") (pin "3") (pinfunction "D_3") (pintype "passive"))
    )
    (net (code "40") (name "Net-(U1-V3)") (class "Default")
      (node (ref "C7") (pin "2") (pinfunction "2_2") (pintype "passive"))
      (node (ref "U1") (pin "4") (pinfunction "V3_4") (pintype "bidirectional"))
    )
    (net (code "41") (name "RESET") (class "Default")
      (node (ref "CN5") (pin "5") (pinfunction "5_5") (pintype "bidirectional"))
      (node (ref "CN6") (pin "6") (pinfunction "6_6") (pintype "passive"))
      (node (ref "R12") (pin "1") (pinfunction "1_1") (pintype "passive"))
      (node (ref "S1") (pin "3") (pinfunction "2_3") (pintype "passive"))
      (node (ref "SJ1") (pin "2") (pinfunction "2_2") (pintype "passive"))
      (node (ref "U2") (pin "29") (pinfunction "PC6(/RESET)_29") (pintype "bidirectional"))
      (node (ref "U3") (pin "25") (pinfunction "PC6(/RESET)_25") (pintype "bidirectional"))
    )
    (net (code "42") (name "USB_DTR") (class "Default")
      (node (ref "C18") (pin "1") (pinfunction "1_1") (pintype "passive"))
      (node (ref "R11") (pin "2") (pinfunction "2_2") (pintype "passive"))
      (node (ref "U1") (pin "13") (pinfunction "~{DTR}_13") (pintype "bidirectional"))
    )
    (net (code "43") (name "USB_D_M") (class "Default")
      (node (ref "R1") (pin "2") (pinfunction "2_2") (pintype "passive"))
      (node (ref "U1") (pin "6") (pinfunction "UD-_6") (pintype "bidirectional"))
    )
    (net (code "44") (name "USB_D_P") (class "Default")
      (node (ref "R2") (pin "2") (pinfunction "2_2") (pintype "passive"))
      (node (ref "U1") (pin "5") (pinfunction "UD+_5") (pintype "bidirectional"))
    )
    (net (code "45") (name "USB_OSC_IN") (class "Default")
      (node (ref "C9") (pin "2") (pinfunction "2_2") (pintype "passive"))
      (node (ref "Q1") (pin "3") (pinfunction "2_3") (pintype "passive"))
      (node (ref "R3") (pin "2") (pinfunction "2_2") (pintype "passive"))
      (node (ref "U1") (pin "7") (pinfunction "XI_7") (pintype "bidirectional"))
    )
    (net (code "46") (name "USB_OSC_OUT") (class "Default")
      (node (ref "C10") (pin "2") (pinfunction "2_2") (pintype "passive"))
      (node (ref "Q1") (pin "1") (pinfunction "1_1") (pintype "passive"))
      (node (ref "R3") (pin "1") (pinfunction "1_1") (pintype "passive"))
      (node (ref "U1") (pin "8") (pinfunction "XO_8") (pintype "bidirectional"))
    )
    (net (code "47") (name "USB_SHIELD") (class "Default")
      (node (ref "CN2") (pin "SH1") (pinfunction "SHIELD_SH1") (pintype "passive"))
      (node (ref "CN2") (pin "SH2") (pinfunction "SHIELD_SH2") (pintype "passive"))
      (node (ref "CN2") (pin "SH3") (pinfunction "SHIELD_SH3") (pintype "passive"))
      (node (ref "CN2") (pin "SH4") (pinfunction "SHIELD_SH4") (pintype "passive"))
      (node (ref "CN2") (pin "SH5") (pinfunction "SHIELD_SH5") (pintype "passive"))
      (node (ref "CN2") (pin "SH6") (pinfunction "SHIELD_SH6") (pintype "passive"))
    )
    (net (code "48") (name "VIN") (class "Default")
      (node (ref "CN1") (pin "PWR") (pinfunction "PWR_PWR") (pintype "bidirectional"))
      (node (ref "CN6") (pin "1") (pinfunction "1_1") (pintype "passive"))
      (node (ref "D1") (pin "2") (pinfunction "A_2") (pintype "passive"))
      (node (ref "R4") (pin "2") (pinfunction "2_2") (pintype "passive"))
    )
    (net (code "49") (name "VUSB") (class "Default")
      (node (ref "L2") (pin "2") (pinfunction "2_2") (pintype "passive"))
      (node (ref "T1") (pin "3") (pinfunction "D_3") (pintype "passive"))
    )
    (net (code "50") (name "XUSB") (class "Default")
      (node (ref "CN2") (pin "1") (pinfunction "VBUS_1") (pintype "power_in"))
      (node (ref "F2") (pin "1") (pinfunction "1_1") (pintype "passive"))
    )
    (net (code "51") (name "XUSB_D_M") (class "Default")
      (node (ref "CN2") (pin "2") (pinfunction "D-_2") (pintype "bidirectional"))
      (node (ref "R1") (pin "1") (pinfunction "1_1") (pintype "passive"))
    )
    (net (code "52") (name "XUSB_D_P") (class "Default")
      (node (ref "CN2") (pin "3") (pinfunction "D+_3") (pintype "bidirectional"))
      (node (ref "R2") (pin "1") (pinfunction "1_1") (pintype "passive"))
    )
    (net (code "53") (name "unconnected-(CN2-ID-Pad4)") (class "Default")
      (node (ref "CN2") (pin "4") (pinfunction "ID_4") (pintype "passive"))
    )
    (net (code "54") (name "unconnected-(CN6-Pad8)") (class "Default")
      (node (ref "CN6") (pin "8") (pinfunction "8_8") (pintype "passive"))
    )
    (net (code "55") (name "unconnected-(U1-R232-Pad15)") (class "Default")
      (node (ref "U1") (pin "15") (pinfunction "R232_15") (pintype "bidirectional"))
    )
    (net (code "56") (name "unconnected-(U1-~{CTS}-Pad9)") (class "Default")
      (node (ref "U1") (pin "9") (pinfunction "~{CTS}_9") (pintype "bidirectional"))
    )
    (net (code "57") (name "unconnected-(U1-~{DCD}-Pad12)") (class "Default")
      (node (ref "U1") (pin "12") (pinfunction "~{DCD}_12") (pintype "bidirectional"))
    )
    (net (code "58") (name "unconnected-(U1-~{DSR}-Pad10)") (class "Default")
      (node (ref "U1") (pin "10") (pinfunction "~{DSR}_10") (pintype "bidirectional"))
    )
    (net (code "59") (name "unconnected-(U1-~{RI}-Pad11)") (class "Default")
      (node (ref "U1") (pin "11") (pinfunction "~{RI}_11") (pintype "bidirectional"))
    )
    (net (code "60") (name "unconnected-(U1-~{RTS}-Pad14)") (class "Default")
      (node (ref "U1") (pin "14") (pinfunction "~{RTS}_14") (pintype "bidirectional"))
    )
    (net (code "61") (name "unconnected-(U2-ADC6-Pad19)") (class "Default")
      (node (ref "U2") (pin "19") (pinfunction "ADC6_19") (pintype "bidirectional"))
    )
    (net (code "62") (name "unconnected-(U2-ADC7-Pad22)") (class "Default")
      (node (ref "U2") (pin "22") (pinfunction "ADC7_22") (pintype "bidirectional"))
    )
  )
)
